# explorator_breakout_pcb_40mm_v2.net
KiCad netlist of a schematic drawn in EAGLE
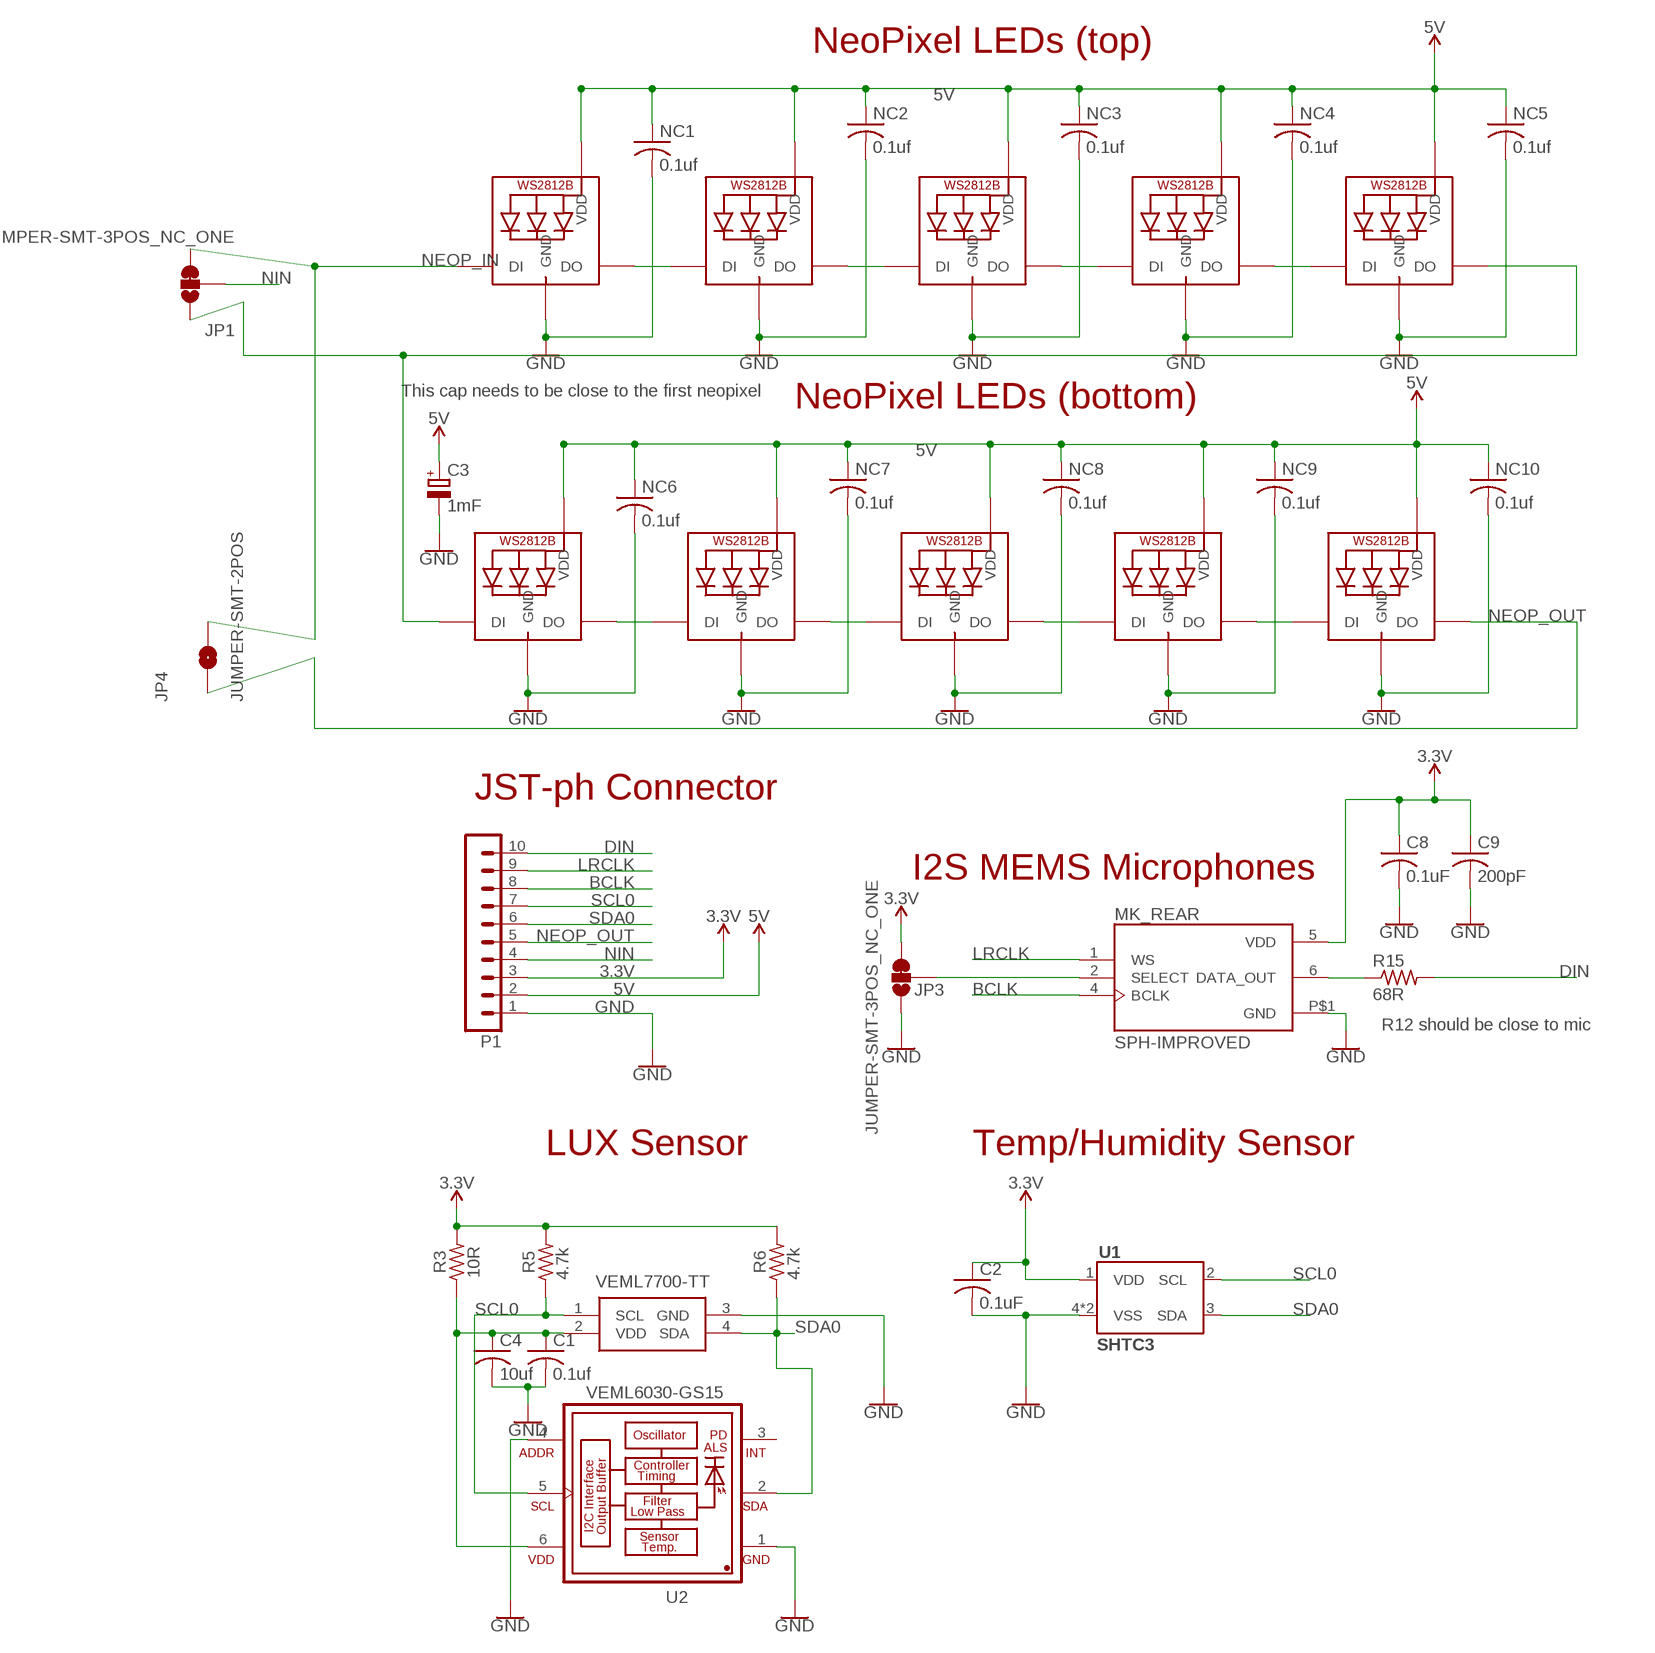
[diagram p0: schematic, sheet 1]

(export (version "E")
  (design (tool "Eeschema 10.0.6"))
  (components
    (comp (ref "C1")
      (value "0.1uf")
      (footprint "eagle-import:C0805")
      (libsource (lib "eagle-import") (part "C-USC0805"))
    )
    (comp (ref "C2")
      (value "0.1uF")
      (footprint "eagle-import:C0805")
      (libsource (lib "eagle-import") (part "C-USC0805"))
    )
    (comp (ref "C3")
      (value "1mF")
      (footprint "eagle-import:153CLV-1012")
      (libsource (lib "eagle-import") (part "CPOL-EU153CLV-1012"))
    )
    (comp (ref "C4")
      (value "10uf")
      (footprint "eagle-import:C0805")
      (libsource (lib "eagle-import") (part "C-USC0805"))
    )
    (comp (ref "C8")
      (value "0.1uF")
      (footprint "eagle-import:C0805")
      (libsource (lib "eagle-import") (part "C-USC0805"))
    )
    (comp (ref "C9")
      (value "200pF")
      (footprint "eagle-import:C0805")
      (libsource (lib "eagle-import") (part "C-USC0805"))
    )
    (comp (ref "JP1")
      (value "JUMPER-SMT-3POS_NC_ONE")
      (footprint "eagle-import:SMT-JUMPER_3_1-NC_TRACE_NO-SILK")
      (libsource (lib "eagle-import") (part "JUMPER-SMT-3POS_NC_ONE"))
    )
    (comp (ref "JP3")
      (value "JUMPER-SMT-3POS_NC_ONE")
      (footprint "eagle-import:SMT-JUMPER_3_1-NC_TRACE_NO-SILK")
      (libsource (lib "eagle-import") (part "JUMPER-SMT-3POS_NC_ONE"))
    )
    (comp (ref "JP4")
      (value "JUMPER-SMT-2POS")
      (footprint "eagle-import:SMT-JUMPER_2_NO_NO-SILK")
      (libsource (lib "eagle-import") (part "JUMPER-SMT-2POS"))
    )
    (comp (ref "MK_REAR")
      (value "SPH-IMPROVED")
      (footprint "eagle-import:MIC_SPH0645LM4H-B_LARGER_RING")
      (libsource (lib "eagle-import") (part "SPH-IMPROVED"))
    )
    (comp (ref "NC1")
      (value "0.1uf")
      (footprint "eagle-import:C0805")
      (libsource (lib "eagle-import") (part "C-USC0805"))
    )
    (comp (ref "NC2")
      (value "0.1uf")
      (footprint "eagle-import:C0805")
      (libsource (lib "eagle-import") (part "C-USC0805"))
    )
    (comp (ref "NC3")
      (value "0.1uf")
      (footprint "eagle-import:C0805")
      (libsource (lib "eagle-import") (part "C-USC0805"))
    )
    (comp (ref "NC4")
      (value "0.1uf")
      (footprint "eagle-import:C0805")
      (libsource (lib "eagle-import") (part "C-USC0805"))
    )
    (comp (ref "NC5")
      (value "0.1uf")
      (footprint "eagle-import:C0805")
      (libsource (lib "eagle-import") (part "C-USC0805"))
    )
    (comp (ref "NC6")
      (value "0.1uf")
      (footprint "eagle-import:C0805")
      (libsource (lib "eagle-import") (part "C-USC0805"))
    )
    (comp (ref "NC7")
      (value "0.1uf")
      (footprint "eagle-import:C0805")
      (libsource (lib "eagle-import") (part "C-USC0805"))
    )
    (comp (ref "NC8")
      (value "0.1uf")
      (footprint "eagle-import:C0805")
      (libsource (lib "eagle-import") (part "C-USC0805"))
    )
    (comp (ref "NC9")
      (value "0.1uf")
      (footprint "eagle-import:C0805")
      (libsource (lib "eagle-import") (part "C-USC0805"))
    )
    (comp (ref "NC10")
      (value "0.1uf")
      (footprint "eagle-import:C0805")
      (libsource (lib "eagle-import") (part "C-USC0805"))
    )
    (comp (ref "NEO_01")
      (value "WS2812")
      (footprint "eagle-import:WS2812B")
      (libsource (lib "eagle-import") (part "WS2812"))
    )
    (comp (ref "NEO_02")
      (value "WS2812")
      (footprint "eagle-import:WS2812B")
      (libsource (lib "eagle-import") (part "WS2812"))
    )
    (comp (ref "NEO_03")
      (value "WS2812")
      (footprint "eagle-import:WS2812B")
      (libsource (lib "eagle-import") (part "WS2812"))
    )
    (comp (ref "NEO_04")
      (value "WS2812")
      (footprint "eagle-import:WS2812B")
      (libsource (lib "eagle-import") (part "WS2812"))
    )
    (comp (ref "NEO_05")
      (value "WS2812")
      (footprint "eagle-import:WS2812B")
      (libsource (lib "eagle-import") (part "WS2812"))
    )
    (comp (ref "NEO_06")
      (value "WS2812")
      (footprint "eagle-import:WS2812B")
      (libsource (lib "eagle-import") (part "WS2812"))
    )
    (comp (ref "NEO_07")
      (value "WS2812")
      (footprint "eagle-import:WS2812B")
      (libsource (lib "eagle-import") (part "WS2812"))
    )
    (comp (ref "NEO_08")
      (value "WS2812")
      (footprint "eagle-import:WS2812B")
      (libsource (lib "eagle-import") (part "WS2812"))
    )
    (comp (ref "NEO_09")
      (value "WS2812")
      (footprint "eagle-import:WS2812B")
      (libsource (lib "eagle-import") (part "WS2812"))
    )
    (comp (ref "NEO_10")
      (value "WS2812")
      (footprint "eagle-import:WS2812B")
      (libsource (lib "eagle-import") (part "WS2812"))
    )
    (comp (ref "P1")
      (value "B10B-PH-K")
      (footprint "eagle-import:B10B-PH-K")
      (libsource (lib "eagle-import") (part "B10B-PH-K"))
    )
    (comp (ref "R3")
      (value "10R")
      (footprint "eagle-import:R0805")
      (libsource (lib "eagle-import") (part "R-US_R0805"))
    )
    (comp (ref "R5")
      (value "4.7k")
      (footprint "eagle-import:R0805")
      (libsource (lib "eagle-import") (part "R-US_R0805"))
    )
    (comp (ref "R6")
      (value "4.7k")
      (footprint "eagle-import:R0805")
      (libsource (lib "eagle-import") (part "R-US_R0805"))
    )
    (comp (ref "R15")
      (value "68R")
      (footprint "eagle-import:R0805")
      (libsource (lib "eagle-import") (part "R-US_R0805"))
    )
    (comp (ref "U1")
      (value "SHTC3")
      (footprint "eagle-import:SHTC3")
      (libsource (lib "eagle-import") (part "SHTC3"))
    )
    (comp (ref "U2")
      (value "VEML6030-GS15")
      (footprint "eagle-import:VISHAY_VEML6030_2X2X0.87")
      (fields (field (name "MF") "Vishay Semiconductor"))
      (libsource (lib "eagle-import") (part "VEML6030-GS15"))
    )
    (comp (ref "VEML_F")
      (value "VEML7700-TT")
      (footprint "eagle-import:VEML7700")
      (fields (field (name "MOUSER_PART_NUMBER") "78-VEML7700-TT") (field (name "RS_PART_NUMBER") "1226791P"))
      (libsource (lib "eagle-import") (part "VEML7700-TT"))
    )
  )
  (nets
    (net (code "1") (name "/BCLK") (class "Default")
      (node (ref "MK_REAR") (pin "4") (pinfunction "BCLK_4") (pintype "input"))
      (node (ref "P1") (pin "8") (pinfunction "8_8") (pintype "passive"))
    )
    (net (code "2") (name "/DIN") (class "Default")
      (node (ref "P1") (pin "10") (pinfunction "10_10") (pintype "passive"))
      (node (ref "R15") (pin "2") (pinfunction "2_2") (pintype "passive"))
    )
    (net (code "3") (name "/LRCLK") (class "Default")
      (node (ref "MK_REAR") (pin "1") (pinfunction "WS_1") (pintype "input"))
      (node (ref "P1") (pin "9") (pinfunction "9_9") (pintype "passive"))
    )
    (net (code "4") (name "/NEOP_IN") (class "Default")
      (node (ref "JP1") (pin "3") (pinfunction "3_3") (pintype "passive"))
      (node (ref "JP4") (pin "2") (pinfunction "2_2") (pintype "passive"))
      (node (ref "NEO_01") (pin "4-DIN") (pinfunction "DI_4-DIN") (pintype "input"))
    )
    (net (code "5") (name "/NEOP_OUT") (class "Default")
      (node (ref "JP4") (pin "1") (pinfunction "1_1") (pintype "passive"))
      (node (ref "NEO_10") (pin "2-DOUT") (pinfunction "DO_2-DOUT") (pintype "output"))
      (node (ref "P1") (pin "5") (pinfunction "5_5") (pintype "passive"))
    )
    (net (code "6") (name "/NIN") (class "Default")
      (node (ref "JP1") (pin "2") (pinfunction "2_2") (pintype "passive"))
      (node (ref "P1") (pin "4") (pinfunction "4_4") (pintype "passive"))
    )
    (net (code "7") (name "/SCL0") (class "Default")
      (node (ref "P1") (pin "7") (pinfunction "7_7") (pintype "passive"))
      (node (ref "R5") (pin "1") (pinfunction "1_1") (pintype "passive"))
      (node (ref "U1") (pin "2") (pinfunction "SCL_2") (pintype "bidirectional"))
      (node (ref "U2") (pin "5") (pinfunction "SCL_5") (pintype "input"))
      (node (ref "VEML_F") (pin "1") (pinfunction "SCL_1") (pintype "bidirectional"))
    )
    (net (code "8") (name "/SDA0") (class "Default")
      (node (ref "P1") (pin "6") (pinfunction "6_6") (pintype "passive"))
      (node (ref "R6") (pin "1") (pinfunction "1_1") (pintype "passive"))
      (node (ref "U1") (pin "3") (pinfunction "SDA_3") (pintype "bidirectional"))
      (node (ref "U2") (pin "2") (pinfunction "SDA_2") (pintype "bidirectional"))
      (node (ref "VEML_F") (pin "4") (pinfunction "SDA_4") (pintype "bidirectional"))
    )
    (net (code "9") (name "3.3V") (class "Default")
      (node (ref "C2") (pin "1") (pinfunction "1_1") (pintype "passive"))
      (node (ref "C8") (pin "1") (pinfunction "1_1") (pintype "passive"))
      (node (ref "C9") (pin "1") (pinfunction "1_1") (pintype "passive"))
      (node (ref "JP3") (pin "3") (pinfunction "3_3") (pintype "passive"))
      (node (ref "MK_REAR") (pin "5") (pinfunction "VDD_5") (pintype "power_in"))
      (node (ref "P1") (pin "3") (pinfunction "3_3") (pintype "passive"))
      (node (ref "R3") (pin "2") (pinfunction "2_2") (pintype "passive"))
      (node (ref "R5") (pin "2") (pinfunction "2_2") (pintype "passive"))
      (node (ref "R6") (pin "2") (pinfunction "2_2") (pintype "passive"))
      (node (ref "U1") (pin "1") (pinfunction "VDD_1") (pintype "bidirectional"))
    )
    (net (code "10") (name "5V") (class "Default")
      (node (ref "C3") (pin "+") (pinfunction "+_+") (pintype "passive"))
      (node (ref "NC1") (pin "1") (pinfunction "1_1") (pintype "passive"))
      (node (ref "NC10") (pin "1") (pinfunction "1_1") (pintype "passive"))
      (node (ref "NC2") (pin "1") (pinfunction "1_1") (pintype "passive"))
      (node (ref "NC3") (pin "1") (pinfunction "1_1") (pintype "passive"))
      (node (ref "NC4") (pin "1") (pinfunction "1_1") (pintype "passive"))
      (node (ref "NC5") (pin "1") (pinfunction "1_1") (pintype "passive"))
      (node (ref "NC6") (pin "1") (pinfunction "1_1") (pintype "passive"))
      (node (ref "NC7") (pin "1") (pinfunction "1_1") (pintype "passive"))
      (node (ref "NC8") (pin "1") (pinfunction "1_1") (pintype "passive"))
      (node (ref "NC9") (pin "1") (pinfunction "1_1") (pintype "passive"))
      (node (ref "NEO_01") (pin "1-VDD") (pinfunction "VDD_1-VDD") (pintype "power_in"))
      (node (ref "NEO_02") (pin "1-VDD") (pinfunction "VDD_1-VDD") (pintype "power_in"))
      (node (ref "NEO_03") (pin "1-VDD") (pinfunction "VDD_1-VDD") (pintype "power_in"))
      (node (ref "NEO_04") (pin "1-VDD") (pinfunction "VDD_1-VDD") (pintype "power_in"))
      (node (ref "NEO_05") (pin "1-VDD") (pinfunction "VDD_1-VDD") (pintype "power_in"))
      (node (ref "NEO_06") (pin "1-VDD") (pinfunction "VDD_1-VDD") (pintype "power_in"))
      (node (ref "NEO_07") (pin "1-VDD") (pinfunction "VDD_1-VDD") (pintype "power_in"))
      (node (ref "NEO_08") (pin "1-VDD") (pinfunction "VDD_1-VDD") (pintype "power_in"))
      (node (ref "NEO_09") (pin "1-VDD") (pinfunction "VDD_1-VDD") (pintype "power_in"))
      (node (ref "NEO_10") (pin "1-VDD") (pinfunction "VDD_1-VDD") (pintype "power_in"))
      (node (ref "P1") (pin "2") (pinfunction "2_2") (pintype "passive"))
    )
    (net (code "11") (name "GND") (class "Default")
      (node (ref "C1") (pin "2") (pinfunction "2_2") (pintype "passive"))
      (node (ref "C2") (pin "2") (pinfunction "2_2") (pintype "passive"))
      (node (ref "C3") (pin "-") (pinfunction "-_-") (pintype "passive"))
      (node (ref "C4") (pin "2") (pinfunction "2_2") (pintype "passive"))
      (node (ref "C8") (pin "2") (pinfunction "2_2") (pintype "passive"))
      (node (ref "C9") (pin "2") (pinfunction "2_2") (pintype "passive"))
      (node (ref "JP3") (pin "1") (pinfunction "1_1") (pintype "passive"))
      (node (ref "MK_REAR") (pin "P$1") (pinfunction "GND_P$1") (pintype "power_in"))
      (node (ref "NC1") (pin "2") (pinfunction "2_2") (pintype "passive"))
      (node (ref "NC10") (pin "2") (pinfunction "2_2") (pintype "passive"))
      (node (ref "NC2") (pin "2") (pinfunction "2_2") (pintype "passive"))
      (node (ref "NC3") (pin "2") (pinfunction "2_2") (pintype "passive"))
      (node (ref "NC4") (pin "2") (pinfunction "2_2") (pintype "passive"))
      (node (ref "NC5") (pin "2") (pinfunction "2_2") (pintype "passive"))
      (node (ref "NC6") (pin "2") (pinfunction "2_2") (pintype "passive"))
      (node (ref "NC7") (pin "2") (pinfunction "2_2") (pintype "passive"))
      (node (ref "NC8") (pin "2") (pinfunction "2_2") (pintype "passive"))
      (node (ref "NC9") (pin "2") (pinfunction "2_2") (pintype "passive"))
      (node (ref "NEO_01") (pin "3-GND") (pinfunction "GND_3-GND") (pintype "power_in"))
      (node (ref "NEO_02") (pin "3-GND") (pinfunction "GND_3-GND") (pintype "power_in"))
      (node (ref "NEO_03") (pin "3-GND") (pinfunction "GND_3-GND") (pintype "power_in"))
      (node (ref "NEO_04") (pin "3-GND") (pinfunction "GND_3-GND") (pintype "power_in"))
      (node (ref "NEO_05") (pin "3-GND") (pinfunction "GND_3-GND") (pintype "power_in"))
      (node (ref "NEO_06") (pin "3-GND") (pinfunction "GND_3-GND") (pintype "power_in"))
      (node (ref "NEO_07") (pin "3-GND") (pinfunction "GND_3-GND") (pintype "power_in"))
      (node (ref "NEO_08") (pin "3-GND") (pinfunction "GND_3-GND") (pintype "power_in"))
      (node (ref "NEO_09") (pin "3-GND") (pinfunction "GND_3-GND") (pintype "power_in"))
      (node (ref "NEO_10") (pin "3-GND") (pinfunction "GND_3-GND") (pintype "power_in"))
      (node (ref "P1") (pin "1") (pinfunction "1_1") (pintype "passive"))
      (node (ref "U1") (pin "4") (pinfunction "VSS_4") (pintype "bidirectional"))
      (node (ref "U1") (pin "5") (pinfunction "VSS_5") (pintype "bidirectional"))
      (node (ref "U2") (pin "1") (pinfunction "GND_1") (pintype "power_in"))
      (node (ref "U2") (pin "4") (pinfunction "ADDR_4") (pintype "bidirectional"))
      (node (ref "VEML_F") (pin "3") (pinfunction "GND_3") (pintype "bidirectional"))
    )
    (net (code "12") (name "Net-(MK_REAR-DATA_OUT)") (class "Default")
      (node (ref "MK_REAR") (pin "6") (pinfunction "DATA_OUT_6") (pintype "output"))
      (node (ref "R15") (pin "1") (pinfunction "1_1") (pintype "passive"))
    )
    (net (code "13") (name "Net-(MK_REAR-SELECT)") (class "Default")
      (node (ref "JP3") (pin "2") (pinfunction "2_2") (pintype "passive"))
      (node (ref "MK_REAR") (pin "2") (pinfunction "SELECT_2") (pintype "input"))
    )
    (net (code "14") (name "Net-(NEO_01-DO)") (class "Default")
      (node (ref "NEO_01") (pin "2-DOUT") (pinfunction "DO_2-DOUT") (pintype "output"))
      (node (ref "NEO_02") (pin "4-DIN") (pinfunction "DI_4-DIN") (pintype "input"))
    )
    (net (code "15") (name "Net-(NEO_02-DO)") (class "Default")
      (node (ref "NEO_02") (pin "2-DOUT") (pinfunction "DO_2-DOUT") (pintype "output"))
      (node (ref "NEO_03") (pin "4-DIN") (pinfunction "DI_4-DIN") (pintype "input"))
    )
    (net (code "16") (name "Net-(NEO_03-DO)") (class "Default")
      (node (ref "NEO_03") (pin "2-DOUT") (pinfunction "DO_2-DOUT") (pintype "output"))
      (node (ref "NEO_04") (pin "4-DIN") (pinfunction "DI_4-DIN") (pintype "input"))
    )
    (net (code "17") (name "Net-(NEO_04-DO)") (class "Default")
      (node (ref "NEO_04") (pin "2-DOUT") (pinfunction "DO_2-DOUT") (pintype "output"))
      (node (ref "NEO_05") (pin "4-DIN") (pinfunction "DI_4-DIN") (pintype "input"))
    )
    (net (code "18") (name "Net-(NEO_05-DO)") (class "Default")
      (node (ref "JP1") (pin "1") (pinfunction "1_1") (pintype "passive"))
      (node (ref "NEO_05") (pin "2-DOUT") (pinfunction "DO_2-DOUT") (pintype "output"))
      (node (ref "NEO_06") (pin "4-DIN") (pinfunction "DI_4-DIN") (pintype "input"))
    )
    (net (code "19") (name "Net-(NEO_06-DO)") (class "Default")
      (node (ref "NEO_06") (pin "2-DOUT") (pinfunction "DO_2-DOUT") (pintype "output"))
      (node (ref "NEO_07") (pin "4-DIN") (pinfunction "DI_4-DIN") (pintype "input"))
    )
    (net (code "20") (name "Net-(NEO_07-DO)") (class "Default")
      (node (ref "NEO_07") (pin "2-DOUT") (pinfunction "DO_2-DOUT") (pintype "output"))
      (node (ref "NEO_08") (pin "4-DIN") (pinfunction "DI_4-DIN") (pintype "input"))
    )
    (net (code "21") (name "Net-(NEO_08-DO)") (class "Default")
      (node (ref "NEO_08") (pin "2-DOUT") (pinfunction "DO_2-DOUT") (pintype "output"))
      (node (ref "NEO_09") (pin "4-DIN") (pinfunction "DI_4-DIN") (pintype "input"))
    )
    (net (code "22") (name "Net-(NEO_09-DO)") (class "Default")
      (node (ref "NEO_09") (pin "2-DOUT") (pinfunction "DO_2-DOUT") (pintype "output"))
      (node (ref "NEO_10") (pin "4-DIN") (pinfunction "DI_4-DIN") (pintype "input"))
    )
    (net (code "23") (name "Net-(U2-VDD)") (class "Default")
      (node (ref "C1") (pin "1") (pinfunction "1_1") (pintype "passive"))
      (node (ref "C4") (pin "1") (pinfunction "1_1") (pintype "passive"))
      (node (ref "R3") (pin "1") (pinfunction "1_1") (pintype "passive"))
      (node (ref "U2") (pin "6") (pinfunction "VDD_6") (pintype "power_in"))
      (node (ref "VEML_F") (pin "2") (pinfunction "VDD_2") (pintype "bidirectional"))
    )
    (net (code "24") (name "unconnected-(U2-INT-Pad3)") (class "Default")
      (node (ref "U2") (pin "3") (pinfunction "INT_3") (pintype "output"))
    )
  )
)
